# Sheet1.net
KiCad netlist of a schematic drawn in Altium Designer
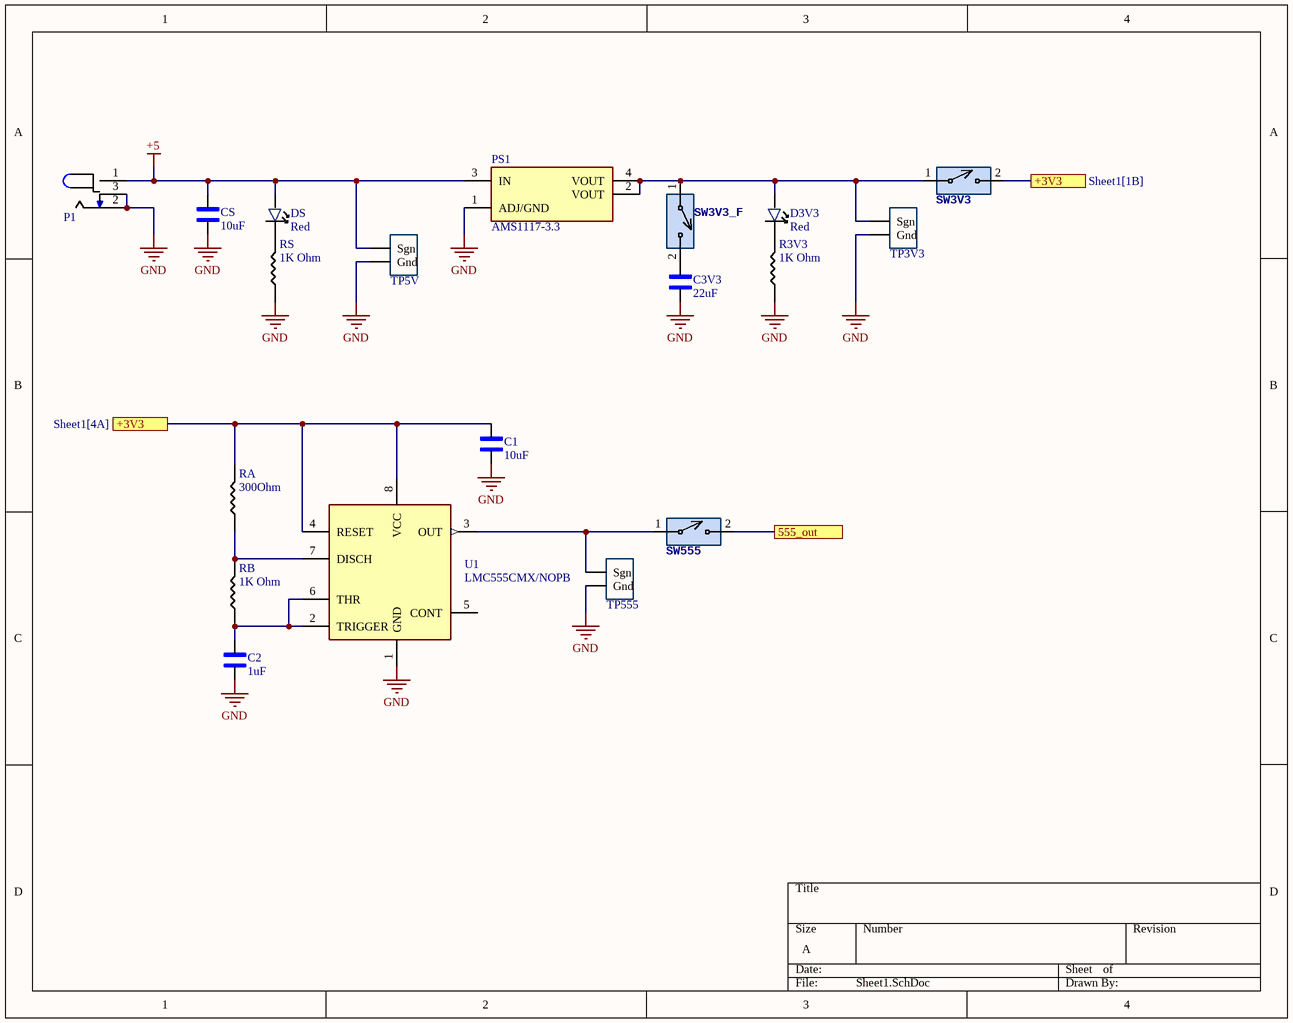
[diagram p0: Sheet1.SchDoc]

(export (version "E")
  (design (tool "Eeschema 10.0.6"))
  (components
    (comp (ref "C1")
      (value "10uF")
      (footprint "1206_Passive_Capacitor")
      (description "10uF ±10% 50V X5R 1206 Multilayer Ceramic Capacitors MLCC - SMD/SMT RoHS")
      (fields (field (name "LCSC PART#") "C13585") (field (name "MFR PART #") "CL31A106KBHNNNE"))
      (libsource (lib "ECEN5730Lib") (part "C_10uF_1206"))
    )
    (comp (ref "C2")
      (value "1uF")
      (footprint "1206_Passive_Capacitor")
      (description "MULTILAYER CERAMIC CAPACITORS MLCC - SMD/SMT 1UF 50V 1206 ROHS")
      (fields (field (name "MFR PART #") "CL31B105KBHNNNE") (field (name "LCSC PART#") "C1848"))
      (libsource (lib "ECEN5730Lib") (part "C_1uF_1206"))
    )
    (comp (ref "C3V3")
      (value "22uF")
      (footprint "1206_Passive_Capacitor")
      (description "22uF ±10% 25V X5R 1206 Multilayer Ceramic Capacitors MLCC - SMD/SMT RoHS")
      (fields (field (name "MFR PART #") "CL31A226KAHNNNE") (field (name "LCSC PART#") "C12891"))
      (libsource (lib "ECEN5730Lib") (part "C_22uF_1206"))
    )
    (comp (ref "CS")
      (value "10uF")
      (footprint "1206_Passive_Capacitor")
      (description "10uF ±10% 50V X5R 1206 Multilayer Ceramic Capacitors MLCC - SMD/SMT RoHS")
      (fields (field (name "LCSC PART#") "C13585") (field (name "MFR PART #") "CL31A106KBHNNNE"))
      (libsource (lib "ECEN5730Lib") (part "C_10uF_1206"))
    )
    (comp (ref "D3V3")
      (value "Red")
      (footprint "LED_1206")
      (description "Red 621~631nm 1206 Light Emitting Diodes (LED) RoHS")
      (fields (field (name "MFR PART #") "15-21/R6C-FQ1R1B/2T") (field (name "LCSC PART#") "C93133"))
      (libsource (lib "ECEN5730Lib") (part "LED_RED_1206"))
    )
    (comp (ref "DS")
      (value "Red")
      (footprint "LED_1206")
      (description "Red 621~631nm 1206 Light Emitting Diodes (LED) RoHS")
      (fields (field (name "MFR PART #") "15-21/R6C-FQ1R1B/2T") (field (name "LCSC PART#") "C93133"))
      (libsource (lib "ECEN5730Lib") (part "LED_RED_1206"))
    )
    (comp (ref "P1")
      (value "Power Jack")
      (footprint "Power_Jack")
      (description "Power Barrel Connector Jack 2.10mm ID (0.083\"), 5.50mm OD (0.217\") Through Hole, Right Angle")
      (fields (field (name "MFR PART #") "PJ-102A") (field (name "LCSC PART#") "C136744"))
      (libsource (lib "ECEN5730Lib") (part "P_Power Jack"))
    )
    (comp (ref "PS1")
      (value "AMS1117-3.3")
      (footprint "LDO")
      (description "LOW DROPOUT REGULATORS(LDO) POSITIVE FIXED 1.3V @ 800MA 15V 3.3V 1A SOT-223 ROHS")
      (fields (field (name "LCSC PART#") "C6186"))
      (libsource (lib "ECEN5730Lib") (part "PS_AMS_LDO_3v3"))
    )
    (comp (ref "R3V3")
      (value "1K Ohm")
      (footprint "1206_Passive_Resitor")
      (description "CHIP RESISTOR - SURFACE MOUNT 1KOHMS ±1% 1/4W 1206 ROHS")
      (fields (field (name "MFR PART #") "RNCP1206FTD1K00CT") (field (name "LCSC PART#") "C4410"))
      (libsource (lib "ECEN5730Lib") (part "R_1K_1206"))
    )
    (comp (ref "RA")
      (value "300Ohm")
      (footprint "1206_Passive_Resitor")
      (description "CHIP RESISTOR - SURFACE MOUNT 300OHMS ±1% 1/4W 1206 ROHS")
      (fields (field (name "MFR PART #") "1206W4F3000T5E") (field (name "LCSC PART#") "C17887"))
      (libsource (lib "ECEN5730Lib") (part "R_300Ohm_1206"))
    )
    (comp (ref "RB")
      (value "1K Ohm")
      (footprint "1206_Passive_Resitor")
      (description "CHIP RESISTOR - SURFACE MOUNT 1KOHMS ±1% 1/4W 1206 ROHS")
      (fields (field (name "MFR PART #") "RNCP1206FTD1K00CT") (field (name "LCSC PART#") "C4410"))
      (libsource (lib "ECEN5730Lib") (part "R_1K_1206"))
    )
    (comp (ref "RS")
      (value "1K Ohm")
      (footprint "1206_Passive_Resitor")
      (description "CHIP RESISTOR - SURFACE MOUNT 1KOHMS ±1% 1/4W 1206 ROHS")
      (fields (field (name "MFR PART #") "RNCP1206FTD1K00CT") (field (name "LCSC PART#") "C4410"))
      (libsource (lib "ECEN5730Lib") (part "R_1K_1206"))
    )
    (comp (ref "SW3V3")
      (value "SW_2Pin_100mil_Switch")
      (footprint "2Pin-Header-Conn")
      (description "2Pin Header")
      (fields (field (name "LCSC PART#") "C124375"))
      (libsource (lib "ECEN5730Lib") (part "SW_2Pin_100mil_Switch"))
    )
    (comp (ref "SW3V3_F")
      (value "SW_2Pin_100mil_Switch")
      (footprint "2Pin-Header-Conn")
      (description "2Pin Header")
      (fields (field (name "LCSC PART#") "C124375"))
      (libsource (lib "") (part "SW_2Pin_100mil_Switch_1"))
    )
    (comp (ref "SW555")
      (value "SW_2Pin_100mil_Switch")
      (footprint "2Pin-Header-Conn")
      (description "2Pin Header")
      (fields (field (name "LCSC PART#") "C124375"))
      (libsource (lib "ECEN5730Lib") (part "SW_2Pin_100mil_Switch"))
    )
    (comp (ref "TP3V3")
      (value "10x Probe TP")
      (footprint "TP10x_Probe")
      (description "Test Point 300 mil centers")
      (libsource (lib "ECEN5730Lib") (part "TP_10x_Probe"))
    )
    (comp (ref "TP5V")
      (value "10x Probe TP")
      (footprint "TP10x_Probe")
      (description "Test Point 300 mil centers")
      (libsource (lib "ECEN5730Lib") (part "TP_10x_Probe"))
    )
    (comp (ref "TP555")
      (value "10x Probe TP")
      (footprint "TP10x_Probe")
      (description "Test Point 300 mil centers")
      (libsource (lib "ECEN5730Lib") (part "TP_10x_Probe"))
    )
    (comp (ref "U1")
      (value "LMC555CMX/NOPB")
      (footprint "TS555IDTTR")
      (description "555 Type, Timer/Oscillator _Single_ IC 3MHz 8-SO")
      (fields (field (name "LCSC PART#") "C90760"))
      (libsource (lib "ECEN5730Lib") (part "U_555_Fast"))
    )
  )
  (nets
    (net (code "1") (name "+5") (class "Default")
      (node (ref "CS") (pin "2") (pinfunction "2_2") (pintype "passive"))
      (node (ref "DS") (pin "1") (pinfunction "1_1") (pintype "passive"))
      (node (ref "P1") (pin "1") (pinfunction "1_1") (pintype "power_in"))
      (node (ref "PS1") (pin "3") (pinfunction "IN_3") (pintype "power_in"))
      (node (ref "TP5V") (pin "1") (pinfunction "Sgn_1") (pintype "passive"))
    )
    (net (code "2") (name "/+3V3") (class "Default")
      (node (ref "C1") (pin "2") (pinfunction "2_2") (pintype "passive"))
      (node (ref "RA") (pin "2") (pinfunction "2_2") (pintype "passive"))
      (node (ref "SW3V3") (pin "2") (pinfunction "2_2") (pintype "passive"))
      (node (ref "U1") (pin "4") (pinfunction "RESET_4") (pintype "passive"))
      (node (ref "U1") (pin "8") (pinfunction "VCC_8") (pintype "power_in"))
    )
    (net (code "3") (name "/555_out") (class "Default")
      (node (ref "SW555") (pin "2") (pinfunction "2_2") (pintype "passive"))
    )
    (net (code "4") (name "GND") (class "Default")
      (node (ref "C1") (pin "1") (pinfunction "1_1") (pintype "passive"))
      (node (ref "C2") (pin "1") (pinfunction "1_1") (pintype "passive"))
      (node (ref "C3V3") (pin "1") (pinfunction "1_1") (pintype "passive"))
      (node (ref "CS") (pin "1") (pinfunction "1_1") (pintype "passive"))
      (node (ref "P1") (pin "2") (pinfunction "2_2") (pintype "power_in"))
      (node (ref "P1") (pin "3") (pinfunction "3_3") (pintype "power_in"))
      (node (ref "PS1") (pin "1") (pinfunction "ADJ/GND_1") (pintype "passive"))
      (node (ref "R3V3") (pin "1") (pinfunction "1_1") (pintype "passive"))
      (node (ref "RS") (pin "1") (pinfunction "1_1") (pintype "passive"))
      (node (ref "TP3V3") (pin "2") (pinfunction "Gnd_2") (pintype "passive"))
      (node (ref "TP555") (pin "2") (pinfunction "Gnd_2") (pintype "passive"))
      (node (ref "TP5V") (pin "2") (pinfunction "Gnd_2") (pintype "passive"))
      (node (ref "U1") (pin "1") (pinfunction "GND_1") (pintype "power_in"))
    )
    (net (code "5") (name "Net-(C3V3-Pad2)") (class "Default")
      (node (ref "C3V3") (pin "2") (pinfunction "2_2") (pintype "passive"))
      (node (ref "SW3V3_F") (pin "2") (pinfunction "2_2") (pintype "passive"))
    )
    (net (code "6") (name "Net-(D3V3-Pad2)") (class "Default")
      (node (ref "D3V3") (pin "2") (pinfunction "2_2") (pintype "passive"))
      (node (ref "R3V3") (pin "2") (pinfunction "2_2") (pintype "passive"))
    )
    (net (code "7") (name "Net-(DS-Pad2)") (class "Default")
      (node (ref "DS") (pin "2") (pinfunction "2_2") (pintype "passive"))
      (node (ref "RS") (pin "2") (pinfunction "2_2") (pintype "passive"))
    )
    (net (code "8") (name "Net-(TP3V3-Sgn)") (class "Default")
      (node (ref "D3V3") (pin "1") (pinfunction "1_1") (pintype "passive"))
      (node (ref "PS1") (pin "2") (pinfunction "VOUT_2") (pintype "power_in"))
      (node (ref "PS1") (pin "4") (pinfunction "VOUT_4") (pintype "power_in"))
      (node (ref "SW3V3") (pin "1") (pinfunction "1_1") (pintype "passive"))
      (node (ref "SW3V3_F") (pin "1") (pinfunction "1_1") (pintype "passive"))
      (node (ref "TP3V3") (pin "1") (pinfunction "Sgn_1") (pintype "passive"))
    )
    (net (code "9") (name "Net-(TP555-Sgn)") (class "Default")
      (node (ref "SW555") (pin "1") (pinfunction "1_1") (pintype "passive"))
      (node (ref "TP555") (pin "1") (pinfunction "Sgn_1") (pintype "passive"))
      (node (ref "U1") (pin "3") (pinfunction "OUT_3") (pintype "output"))
    )
    (net (code "10") (name "Net-(U1-DISCH)") (class "Default")
      (node (ref "RA") (pin "1") (pinfunction "1_1") (pintype "passive"))
      (node (ref "RB") (pin "2") (pinfunction "2_2") (pintype "passive"))
      (node (ref "U1") (pin "7") (pinfunction "DISCH_7") (pintype "passive"))
    )
    (net (code "11") (name "Net-(U1-THR)") (class "Default")
      (node (ref "C2") (pin "2") (pinfunction "2_2") (pintype "passive"))
      (node (ref "RB") (pin "1") (pinfunction "1_1") (pintype "passive"))
      (node (ref "U1") (pin "2") (pinfunction "TRIGGER_2") (pintype "passive"))
      (node (ref "U1") (pin "6") (pinfunction "THR_6") (pintype "passive"))
    )
    (net (code "12") (name "unconnected-(U1-CONT-Pad5)") (class "Default")
      (node (ref "U1") (pin "5") (pinfunction "CONT_5") (pintype "passive"))
    )
  )
)
